# LED.net
KiCad netlist of a schematic drawn in EasyEDA Pro
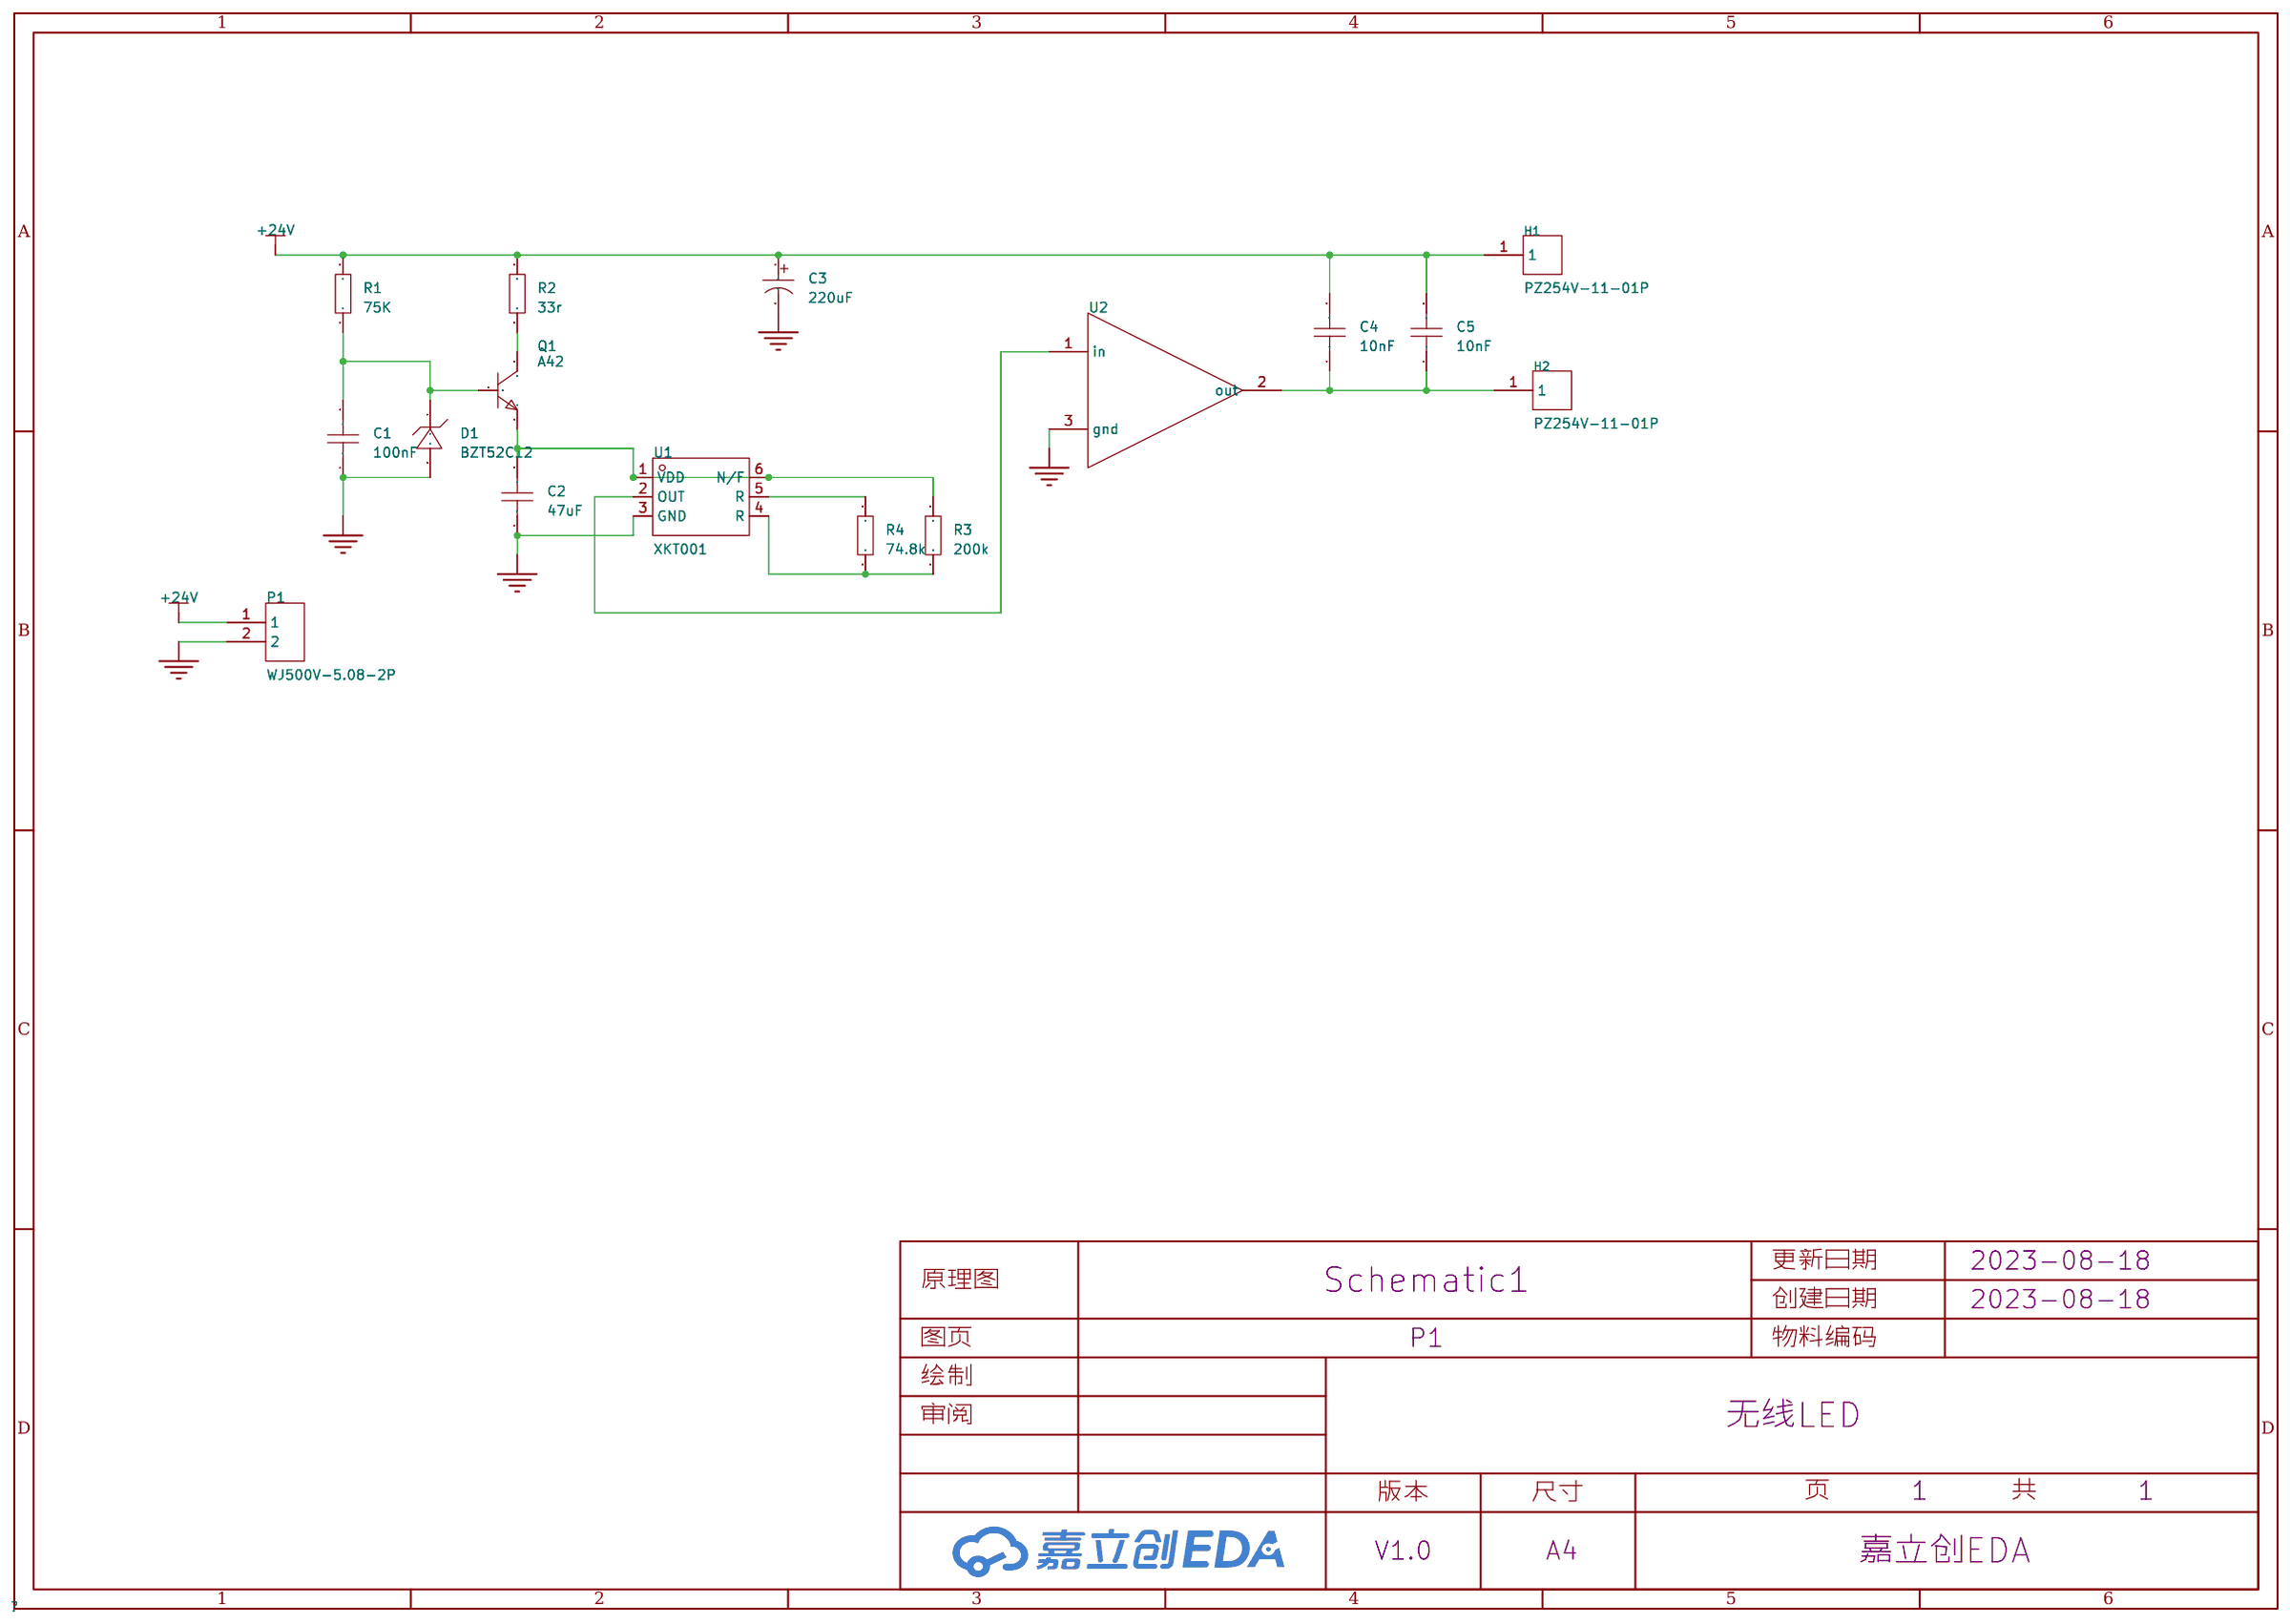
[diagram p0: schematic sheet]

(export (version "E")
  (design (tool "Eeschema 10.0.6"))
  (components
    (comp (ref "C1")
      (value "100nF")
      (footprint "easyedapro:C0603")
      (libsource (lib "easyedapro") (part "CapAcitance"))
    )
    (comp (ref "C2")
      (value "47uF")
      (footprint "easyedapro:C1210")
      (description "容值:47uF;精度:±10%;额定电压:16V;材质(温度系数):X5R;")
      (fields
        (field (name "Manufacturer Part") "GRM32ER61C476KE15L")
        (field (name "Manufacturer") "muRata(村田)")
      )
      (libsource (lib "easyedapro") (part "GRM32ER61C476KE15L"))
    )
    (comp (ref "C3")
      (value "220uF")
      (footprint "easyedapro:CAP-TH_BD8.0-P3.50-D0.6-FD")
      (description "容值:220uF;精度:±20%;额定电压:35V;纹波电流:-;等效串联电阻:-;")
      (fields
        (field (name "Manufacturer Part") "KM227M035F12RR0VH2FP0")
        (field (name "Manufacturer") "CX(承兴)")
      )
      (libsource (lib "easyedapro") (part "220uf/35V"))
    )
    (comp (ref "C4")
      (value "10nF")
      (footprint "easyedapro:C1210")
      (description "容值:10nF;精度:±5%;额定电压:250V;材质(温度系数):NP0;")
      (fields (field (name "Manufacturer Part") "FM32N103J251EFG") (field (name "Manufacturer") "PSA(信昌电陶)"))
      (libsource (lib "easyedapro") (part "FM32N103J251EFG"))
    )
    (comp (ref "C5")
      (value "10nF")
      (footprint "easyedapro:C1210")
      (description "容值:10nF;精度:±5%;额定电压:250V;材质(温度系数):NP0;")
      (fields (field (name "Manufacturer Part") "FM32N103J251EFG") (field (name "Manufacturer") "PSA(信昌电陶)"))
      (libsource (lib "easyedapro") (part "FM32N103J251EFG"))
    )
    (comp (ref "D1")
      (value "BZT52C12")
      (footprint "easyedapro:SOD-123_L2.7-W1.6-LS3.7-RD")
      (description "二极管配置:独立式;稳压值(标称值):12V;稳压值(范围):11.4V~12.7V;精度:-;功率:500mW;")
      (fields (field (name "Manufacturer") "MDD"))
      (libsource (lib "easyedapro") (part "BZT52C12"))
    )
    (comp (ref "H1")
      (value "PZ254V-11-01P")
      (footprint "easyedapro:HDR-TH_1P-P2.54-V-M")
      (fields (field (name "Manufacturer") "XFCN(兴飞)"))
      (libsource (lib "easyedapro") (part "PZ254V-11-01P"))
    )
    (comp (ref "H2")
      (value "PZ254V-11-01P")
      (footprint "easyedapro:HDR-TH_1P-P2.54-V-M")
      (fields (field (name "Manufacturer") "XFCN(兴飞)"))
      (libsource (lib "easyedapro") (part "PZ254V-11-01P"))
    )
    (comp (ref "P1")
      (value "WJ500V-5.08-2P")
      (footprint "easyedapro:CONN-TH_2P-P5.00_WJ500V-5.08-2P")
      (fields (field (name "Manufacturer") "KANGNEX(康奈克斯电气)"))
      (libsource (lib "easyedapro") (part "WJ500V-5.08-2P-14-00A"))
    )
    (comp (ref "Q1")
      (value "A42")
      (footprint "easyedapro:SOT-89-3_L4.5-W2.5-P1.50-LS4.2-BR")
      (fields (field (name "Manufacturer") "ZRE(治润)"))
      (libsource (lib "easyedapro") (part "A42_C779730"))
    )
    (comp (ref "R1") (value "75K") (footprint "easyedapro:R0603") (libsource (lib "easyedapro") (part "电阻")))
    (comp (ref "R2") (value "33r") (footprint "easyedapro:R0603") (libsource (lib "easyedapro") (part "电阻")))
    (comp (ref "R3") (value "200k") (footprint "easyedapro:R0603") (libsource (lib "easyedapro") (part "电阻")))
    (comp (ref "R4")
      (value "74.8k")
      (footprint "easyedapro:R0603")
      (libsource (lib "easyedapro") (part "电阻"))
    )
    (comp (ref "U1")
      (value "XKT001")
      (footprint "easyedapro:SOT-23-6_L2.9-W1.6-P0.95-LS2.8-BL")
      (libsource (lib "easyedapro") (part "XKT001"))
    )
    (comp (ref "U2")
      (value "~")
      (footprint "easyedapro:PG-TO220-3_L10.0-W4.5-P2.54-L")
      (libsource (lib "easyedapro") (part "XKT1511"))
    )
  )
  (nets
    (net (code "1") (name "+24V") (class "Default")
      (node (ref "C3") (pin "1") (pinfunction "1_1") (pintype "input"))
      (node (ref "C4") (pin "2") (pinfunction "2_2") (pintype "input"))
      (node (ref "C5") (pin "2") (pinfunction "2_2") (pintype "input"))
      (node (ref "H1") (pin "1") (pinfunction "1_1") (pintype "input"))
      (node (ref "P1") (pin "1") (pinfunction "1_1") (pintype "input"))
      (node (ref "R1") (pin "2") (pinfunction "2_2") (pintype "input"))
      (node (ref "R2") (pin "2") (pinfunction "2_2") (pintype "input"))
    )
    (net (code "2") (name "GND") (class "Default")
      (node (ref "C1") (pin "1") (pinfunction "1_1") (pintype "input"))
      (node (ref "C2") (pin "1") (pinfunction "1_1") (pintype "input"))
      (node (ref "C3") (pin "2") (pinfunction "2_2") (pintype "input"))
      (node (ref "D1") (pin "2") (pinfunction "A_2") (pintype "input"))
      (node (ref "P1") (pin "2") (pinfunction "2_2") (pintype "input"))
      (node (ref "U1") (pin "3") (pinfunction "GND_3") (pintype "input"))
      (node (ref "U2") (pin "3") (pinfunction "gnd_3") (pintype "input"))
    )
    (net (code "3") (name "Net-(D1-K)") (class "Default")
      (node (ref "C1") (pin "2") (pinfunction "2_2") (pintype "input"))
      (node (ref "D1") (pin "1") (pinfunction "K_1") (pintype "input"))
      (node (ref "Q1") (pin "1") (pinfunction "B_1") (pintype "input"))
      (node (ref "R1") (pin "1") (pinfunction "1_1") (pintype "input"))
    )
    (net (code "4") (name "Net-(Q1-C)") (class "Default")
      (node (ref "Q1") (pin "2") (pinfunction "C_2") (pintype "input"))
      (node (ref "R2") (pin "1") (pinfunction "1_1") (pintype "input"))
    )
    (net (code "5") (name "Net-(Q1-E)") (class "Default")
      (node (ref "C2") (pin "2") (pinfunction "2_2") (pintype "input"))
      (node (ref "Q1") (pin "3") (pinfunction "E_3") (pintype "input"))
      (node (ref "R3") (pin "2") (pinfunction "2_2") (pintype "input"))
      (node (ref "U1") (pin "1") (pinfunction "VDD_1") (pintype "input"))
      (node (ref "U1") (pin "6") (pinfunction "N/F_6") (pintype "input"))
    )
    (net (code "6") (name "Net-(R3-Pad1)") (class "Default")
      (node (ref "R3") (pin "1") (pinfunction "1_1") (pintype "input"))
      (node (ref "R4") (pin "1") (pinfunction "1_1") (pintype "input"))
      (node (ref "U1") (pin "4") (pinfunction "R_4") (pintype "input"))
    )
    (net (code "7") (name "Net-(R4-Pad2)") (class "Default")
      (node (ref "R4") (pin "2") (pinfunction "2_2") (pintype "input"))
      (node (ref "U1") (pin "5") (pinfunction "R_5") (pintype "input"))
    )
    (net (code "8") (name "Net-(U1-OUT)") (class "Default")
      (node (ref "U1") (pin "2") (pinfunction "OUT_2") (pintype "input"))
      (node (ref "U2") (pin "1") (pinfunction "in_1") (pintype "input"))
    )
    (net (code "9") (name "Net-(U2-out)") (class "Default")
      (node (ref "C4") (pin "1") (pinfunction "1_1") (pintype "input"))
      (node (ref "C5") (pin "1") (pinfunction "1_1") (pintype "input"))
      (node (ref "H2") (pin "1") (pinfunction "1_1") (pintype "input"))
      (node (ref "U2") (pin "2") (pinfunction "out_2") (pintype "input"))
    )
  )
)
